# COM-Isolators.net
KiCad netlist of a schematic drawn in Altium Designer
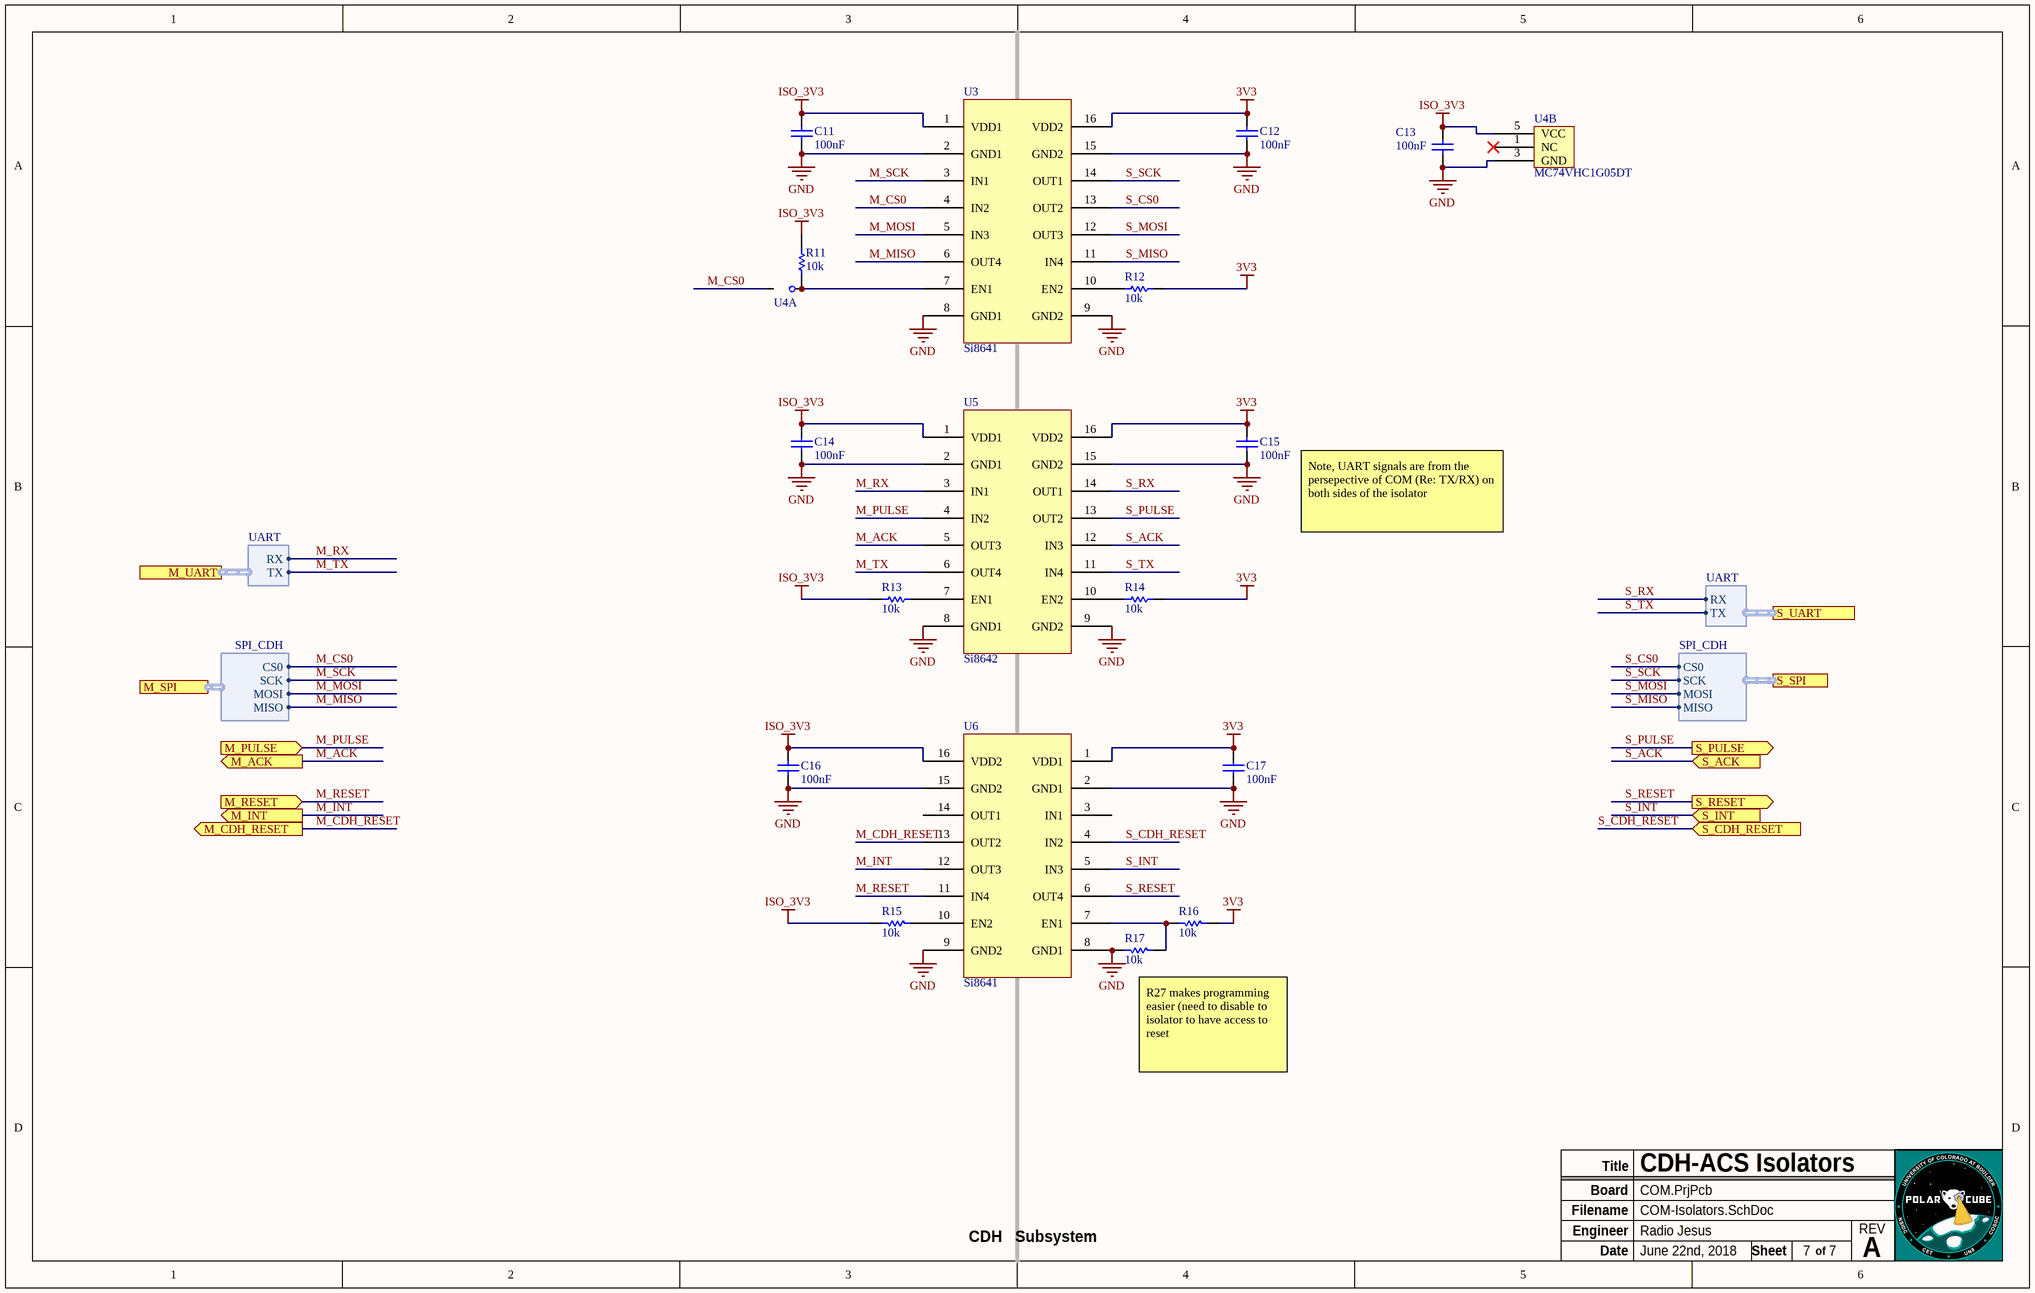
[diagram p0: COM-Isolators.SchDoc]

(export (version "E")
  (design (tool "Eeschema 10.0.6"))
  (components
    (comp (ref "C11")
      (value "CL10B104KB8ZW6C")
      (footprint "1608[0603]")
      (description "MLCC 1608(0603) X7R 100NF 10% 50")
      (fields
        (field (name "CAPACITANCE") "100nF")
        (field (name "PARTNUMBER") "CGA3E2X7R1H104K080AE")
        (field (name "MANUFACTURER") "TDK")
      )
      (libsource (lib "PolarCube") (part "Cap"))
    )
    (comp (ref "C12")
      (value "CL10B104KB8ZW6C")
      (footprint "1608[0603]")
      (description "MLCC 1608(0603) X7R 100NF 10% 50")
      (fields
        (field (name "CAPACITANCE") "100nF")
        (field (name "PARTNUMBER") "CGA3E2X7R1H104K080AE")
        (field (name "MANUFACTURER") "TDK")
      )
      (libsource (lib "PolarCube") (part "Cap"))
    )
    (comp (ref "C13")
      (value "CL10B104KB8ZW6C")
      (footprint "1608[0603]")
      (description "MLCC 1608(0603) X7R 100NF 10% 50")
      (fields
        (field (name "CAPACITANCE") "100nF")
        (field (name "PARTNUMBER") "CGA3E2X7R1H104K080AE")
        (field (name "MANUFACTURER") "TDK")
      )
      (libsource (lib "PolarCube") (part "Cap"))
    )
    (comp (ref "C14")
      (value "CL10B104KB8ZW6C")
      (footprint "1608[0603]")
      (description "MLCC 1608(0603) X7R 100NF 10% 50")
      (fields
        (field (name "CAPACITANCE") "100nF")
        (field (name "PARTNUMBER") "CGA3E2X7R1H104K080AE")
        (field (name "MANUFACTURER") "TDK")
      )
      (libsource (lib "PolarCube") (part "Cap"))
    )
    (comp (ref "C15")
      (value "CL10B104KB8ZW6C")
      (footprint "1608[0603]")
      (description "MLCC 1608(0603) X7R 100NF 10% 50")
      (fields
        (field (name "CAPACITANCE") "100nF")
        (field (name "PARTNUMBER") "CGA3E2X7R1H104K080AE")
        (field (name "MANUFACTURER") "TDK")
      )
      (libsource (lib "PolarCube") (part "Cap"))
    )
    (comp (ref "C16")
      (value "CL10B104KB8ZW6C")
      (footprint "1608[0603]")
      (description "MLCC 1608(0603) X7R 100NF 10% 50")
      (fields
        (field (name "CAPACITANCE") "100nF")
        (field (name "PARTNUMBER") "CGA3E2X7R1H104K080AE")
        (field (name "MANUFACTURER") "TDK")
      )
      (libsource (lib "PolarCube") (part "Cap"))
    )
    (comp (ref "C17")
      (value "CL10B104KB8ZW6C")
      (footprint "1608[0603]")
      (description "MLCC 1608(0603) X7R 100NF 10% 50")
      (fields
        (field (name "CAPACITANCE") "100nF")
        (field (name "PARTNUMBER") "CGA3E2X7R1H104K080AE")
        (field (name "MANUFACTURER") "TDK")
      )
      (libsource (lib "PolarCube") (part "Cap"))
    )
    (comp (ref "R11")
      (value "RMCF0603JG10K0")
      (footprint "1608[0603]")
      (description "10 kOhms ±5% 0.1W, 1/10W Chip Resistor 0603 (1608 Metric) Automotive AEC-Q200 Thick Film")
      (fields
        (field (name "RESISTANCE") "10k")
        (field (name "PARTNUMBER") "CRCW060310K0FKEA")
        (field (name "MANUFACTURER") "Vishay")
      )
      (libsource (lib "PolarCube") (part "Res"))
    )
    (comp (ref "R12")
      (value "RMCF0603JG10K0")
      (footprint "1608[0603]")
      (description "10 kOhms ±5% 0.1W, 1/10W Chip Resistor 0603 (1608 Metric) Automotive AEC-Q200 Thick Film")
      (fields
        (field (name "RESISTANCE") "10k")
        (field (name "PARTNUMBER") "CRCW060310K0FKEA")
        (field (name "MANUFACTURER") "Vishay")
      )
      (libsource (lib "PolarCube") (part "Res"))
    )
    (comp (ref "R13")
      (value "RMCF0603JG10K0")
      (footprint "1608[0603]")
      (description "10 kOhms ±5% 0.1W, 1/10W Chip Resistor 0603 (1608 Metric) Automotive AEC-Q200 Thick Film")
      (fields
        (field (name "RESISTANCE") "10k")
        (field (name "PARTNUMBER") "CRCW060310K0FKEA")
        (field (name "MANUFACTURER") "Vishay")
      )
      (libsource (lib "PolarCube") (part "Res"))
    )
    (comp (ref "R14")
      (value "RMCF0603JG10K0")
      (footprint "1608[0603]")
      (description "10 kOhms ±5% 0.1W, 1/10W Chip Resistor 0603 (1608 Metric) Automotive AEC-Q200 Thick Film")
      (fields
        (field (name "RESISTANCE") "10k")
        (field (name "PARTNUMBER") "CRCW060310K0FKEA")
        (field (name "MANUFACTURER") "Vishay")
      )
      (libsource (lib "PolarCube") (part "Res"))
    )
    (comp (ref "R15")
      (value "RMCF0603JG10K0")
      (footprint "1608[0603]")
      (description "10 kOhms ±5% 0.1W, 1/10W Chip Resistor 0603 (1608 Metric) Automotive AEC-Q200 Thick Film")
      (fields
        (field (name "RESISTANCE") "10k")
        (field (name "PARTNUMBER") "CRCW060310K0FKEA")
        (field (name "MANUFACTURER") "Vishay")
      )
      (libsource (lib "PolarCube") (part "Res"))
    )
    (comp (ref "R16")
      (value "RMCF0603JG10K0")
      (footprint "1608[0603]")
      (description "10 kOhms ±5% 0.1W, 1/10W Chip Resistor 0603 (1608 Metric) Automotive AEC-Q200 Thick Film")
      (fields
        (field (name "RESISTANCE") "10k")
        (field (name "PARTNUMBER") "CRCW060310K0FKEA")
        (field (name "MANUFACTURER") "Vishay")
      )
      (libsource (lib "PolarCube") (part "Res"))
    )
    (comp (ref "R17")
      (value "RMCF0603JG10K0")
      (footprint "1608[0603]")
      (description "10 kOhms ±5% 0.1W, 1/10W Chip Resistor 0603 (1608 Metric) Automotive AEC-Q200 Thick Film")
      (fields
        (field (name "RESISTANCE") "10k")
        (field (name "PARTNUMBER") "CRCW060310K0FKEA")
        (field (name "MANUFACTURER") "Vishay")
      )
      (libsource (lib "PolarCube") (part "Res"))
    )
    (comp (ref "U3")
      (value "Si8641")
      (footprint "SOP64P600X175-16N")
      (description "Low-Power Quad-Channel Digital Isolators")
      (fields (field (name "PARTNUMBER") "SI8641BA-B-IU"))
      (libsource (lib "ACS-Main_SCHLIB") (part "Si8641"))
    )
    (comp (ref "U4")
      (value "MC74VHC1G05DT")
      (footprint "TSOP5")
      (fields (field (name "MANUFACTURER") "ON Semi"))
      (libsource (lib "RAD-Digital") (part "MC74VHC1G05DT"))
    )
    (comp (ref "U5")
      (value "Si8642")
      (footprint "SOP64P600X175-16N")
      (description "Low-Power Quad-Channel Digital Isolators")
      (fields (field (name "PARTNUMBER") "SI8642BA-B-IU"))
      (libsource (lib "COM-MAIN") (part "Si8642"))
    )
    (comp (ref "U6")
      (value "Si8641")
      (footprint "SOP64P600X175-16N")
      (description "Low-Power Quad-Channel Digital Isolators")
      (fields (field (name "PARTNUMBER") "SI8641BA-B-IU"))
      (libsource (lib "") (part "Si8641_1"))
    )
  )
  (nets
    (net (code "3") (name "/M_ACK") (class "Default")
      (node (ref "U5") (pin "5") (pinfunction "OUT3_5") (pintype "passive"))
    )
    (net (code "4") (name "/M_CDH_RESET") (class "Default")
      (node (ref "U6") (pin "13") (pinfunction "OUT2_13") (pintype "passive"))
    )
    (net (code "5") (name "/M_CS0") (class "Default")
      (node (ref "U3") (pin "4") (pinfunction "IN2_4") (pintype "passive"))
      (node (ref "U4") (pin "2") (pinfunction "22_2") (pintype "passive"))
    )
    (net (code "6") (name "/M_INT") (class "Default")
      (node (ref "U6") (pin "12") (pinfunction "OUT3_12") (pintype "passive"))
    )
    (net (code "7") (name "/M_MISO") (class "Default")
      (node (ref "U3") (pin "6") (pinfunction "OUT4_6") (pintype "passive"))
    )
    (net (code "8") (name "/M_MOSI") (class "Default")
      (node (ref "U3") (pin "5") (pinfunction "IN3_5") (pintype "passive"))
    )
    (net (code "9") (name "/M_PULSE") (class "Default")
      (node (ref "U5") (pin "4") (pinfunction "IN2_4") (pintype "passive"))
    )
    (net (code "10") (name "/M_RESET") (class "Default")
      (node (ref "U6") (pin "11") (pinfunction "IN4_11") (pintype "passive"))
    )
    (net (code "11") (name "/M_RX") (class "Default")
      (node (ref "U5") (pin "3") (pinfunction "IN1_3") (pintype "passive"))
    )
    (net (code "12") (name "/M_SCK") (class "Default")
      (node (ref "U3") (pin "3") (pinfunction "IN1_3") (pintype "passive"))
    )
    (net (code "13") (name "/M_TX") (class "Default")
      (node (ref "U5") (pin "6") (pinfunction "OUT4_6") (pintype "passive"))
    )
    (net (code "14") (name "/S_ACK") (class "Default")
      (node (ref "U5") (pin "12") (pinfunction "IN3_12") (pintype "passive"))
    )
    (net (code "15") (name "/S_CDH_RESET") (class "Default")
      (node (ref "U6") (pin "4") (pinfunction "IN2_4") (pintype "passive"))
    )
    (net (code "16") (name "/S_CS0") (class "Default")
      (node (ref "U3") (pin "13") (pinfunction "OUT2_13") (pintype "passive"))
    )
    (net (code "17") (name "/S_INT") (class "Default")
      (node (ref "U6") (pin "5") (pinfunction "IN3_5") (pintype "passive"))
    )
    (net (code "18") (name "/S_MISO") (class "Default")
      (node (ref "U3") (pin "11") (pinfunction "IN4_11") (pintype "passive"))
    )
    (net (code "19") (name "/S_MOSI") (class "Default")
      (node (ref "U3") (pin "12") (pinfunction "OUT3_12") (pintype "passive"))
    )
    (net (code "20") (name "/S_PULSE") (class "Default")
      (node (ref "U5") (pin "13") (pinfunction "OUT2_13") (pintype "passive"))
    )
    (net (code "21") (name "/S_RESET") (class "Default")
      (node (ref "U6") (pin "6") (pinfunction "OUT4_6") (pintype "passive"))
    )
    (net (code "22") (name "/S_RX") (class "Default")
      (node (ref "U5") (pin "14") (pinfunction "OUT1_14") (pintype "passive"))
    )
    (net (code "23") (name "/S_SCK") (class "Default")
      (node (ref "U3") (pin "14") (pinfunction "OUT1_14") (pintype "passive"))
    )
    (net (code "24") (name "/S_TX") (class "Default")
      (node (ref "U5") (pin "11") (pinfunction "IN4_11") (pintype "passive"))
    )
    (net (code "27") (name "3V3") (class "Default")
      (node (ref "C12") (pin "1") (pinfunction "1_1") (pintype "passive"))
      (node (ref "C15") (pin "1") (pinfunction "1_1") (pintype "passive"))
      (node (ref "C17") (pin "1") (pinfunction "1_1") (pintype "passive"))
      (node (ref "R12") (pin "1") (pinfunction "1_1") (pintype "passive"))
      (node (ref "R14") (pin "1") (pinfunction "1_1") (pintype "passive"))
      (node (ref "R16") (pin "2") (pinfunction "2_2") (pintype "passive"))
      (node (ref "U3") (pin "16") (pinfunction "VDD2_16") (pintype "passive"))
      (node (ref "U5") (pin "16") (pinfunction "VDD2_16") (pintype "passive"))
      (node (ref "U6") (pin "1") (pinfunction "VDD1_1") (pintype "passive"))
    )
    (net (code "28") (name "GND") (class "Default")
      (node (ref "C11") (pin "2") (pinfunction "2_2") (pintype "passive"))
      (node (ref "C12") (pin "2") (pinfunction "2_2") (pintype "passive"))
      (node (ref "C13") (pin "2") (pinfunction "2_2") (pintype "passive"))
      (node (ref "C14") (pin "2") (pinfunction "2_2") (pintype "passive"))
      (node (ref "C15") (pin "2") (pinfunction "2_2") (pintype "passive"))
      (node (ref "C16") (pin "2") (pinfunction "2_2") (pintype "passive"))
      (node (ref "C17") (pin "2") (pinfunction "2_2") (pintype "passive"))
      (node (ref "R17") (pin "1") (pinfunction "1_1") (pintype "passive"))
      (node (ref "U3") (pin "15") (pinfunction "GND2_15") (pintype "passive"))
      (node (ref "U3") (pin "2") (pinfunction "GND1_2") (pintype "passive"))
      (node (ref "U3") (pin "8") (pinfunction "GND1_8") (pintype "passive"))
      (node (ref "U3") (pin "9") (pinfunction "GND2_9") (pintype "passive"))
      (node (ref "U4") (pin "3") (pinfunction "GND_3") (pintype "passive"))
      (node (ref "U5") (pin "15") (pinfunction "GND2_15") (pintype "passive"))
      (node (ref "U5") (pin "2") (pinfunction "GND1_2") (pintype "passive"))
      (node (ref "U5") (pin "8") (pinfunction "GND1_8") (pintype "passive"))
      (node (ref "U5") (pin "9") (pinfunction "GND2_9") (pintype "passive"))
      (node (ref "U6") (pin "15") (pinfunction "GND2_15") (pintype "passive"))
      (node (ref "U6") (pin "2") (pinfunction "GND1_2") (pintype "passive"))
      (node (ref "U6") (pin "8") (pinfunction "GND1_8") (pintype "passive"))
      (node (ref "U6") (pin "9") (pinfunction "GND2_9") (pintype "passive"))
    )
    (net (code "29") (name "ISO_3V3") (class "Default")
      (node (ref "C11") (pin "1") (pinfunction "1_1") (pintype "passive"))
      (node (ref "C13") (pin "1") (pinfunction "1_1") (pintype "passive"))
      (node (ref "C14") (pin "1") (pinfunction "1_1") (pintype "passive"))
      (node (ref "C16") (pin "1") (pinfunction "1_1") (pintype "passive"))
      (node (ref "R11") (pin "2") (pinfunction "2_2") (pintype "passive"))
      (node (ref "R13") (pin "2") (pinfunction "2_2") (pintype "passive"))
      (node (ref "R15") (pin "2") (pinfunction "2_2") (pintype "passive"))
      (node (ref "U3") (pin "1") (pinfunction "VDD1_1") (pintype "passive"))
      (node (ref "U4") (pin "5") (pinfunction "VCC_5") (pintype "passive"))
      (node (ref "U5") (pin "1") (pinfunction "VDD1_1") (pintype "passive"))
      (node (ref "U6") (pin "16") (pinfunction "VDD2_16") (pintype "passive"))
    )
    (net (code "30") (name "Net-(U3-EN1)") (class "Default")
      (node (ref "R11") (pin "1") (pinfunction "1_1") (pintype "passive"))
      (node (ref "U3") (pin "7") (pinfunction "EN1_7") (pintype "passive"))
      (node (ref "U4") (pin "4") (pinfunction "23_4") (pintype "passive"))
    )
    (net (code "31") (name "Net-(U3-EN2)") (class "Default")
      (node (ref "R12") (pin "2") (pinfunction "2_2") (pintype "passive"))
      (node (ref "U3") (pin "10") (pinfunction "EN2_10") (pintype "passive"))
    )
    (net (code "32") (name "Net-(U5-EN1)") (class "Default")
      (node (ref "R13") (pin "1") (pinfunction "1_1") (pintype "passive"))
      (node (ref "U5") (pin "7") (pinfunction "EN1_7") (pintype "passive"))
    )
    (net (code "33") (name "Net-(U5-EN2)") (class "Default")
      (node (ref "R14") (pin "2") (pinfunction "2_2") (pintype "passive"))
      (node (ref "U5") (pin "10") (pinfunction "EN2_10") (pintype "passive"))
    )
    (net (code "34") (name "Net-(U6-EN1)") (class "Default")
      (node (ref "R16") (pin "1") (pinfunction "1_1") (pintype "passive"))
      (node (ref "R17") (pin "2") (pinfunction "2_2") (pintype "passive"))
      (node (ref "U6") (pin "7") (pinfunction "EN1_7") (pintype "passive"))
    )
    (net (code "35") (name "Net-(U6-EN2)") (class "Default")
      (node (ref "R15") (pin "1") (pinfunction "1_1") (pintype "passive"))
      (node (ref "U6") (pin "10") (pinfunction "EN2_10") (pintype "passive"))
    )
    (net (code "36") (name "unconnected-(U4B-NC-Pad1)") (class "Default")
      (node (ref "U4") (pin "1") (pinfunction "NC_1") (pintype "passive+no_connect"))
    )
    (net (code "37") (name "unconnected-(U6-IN1-Pad3)") (class "Default")
      (node (ref "U6") (pin "3") (pinfunction "IN1_3") (pintype "passive"))
    )
    (net (code "38") (name "unconnected-(U6-OUT1-Pad14)") (class "Default")
      (node (ref "U6") (pin "14") (pinfunction "OUT1_14") (pintype "passive"))
    )
  )
)
